# 005_PowerRele_OnOff.net
KiCad netlist of a schematic drawn in Altium Designer
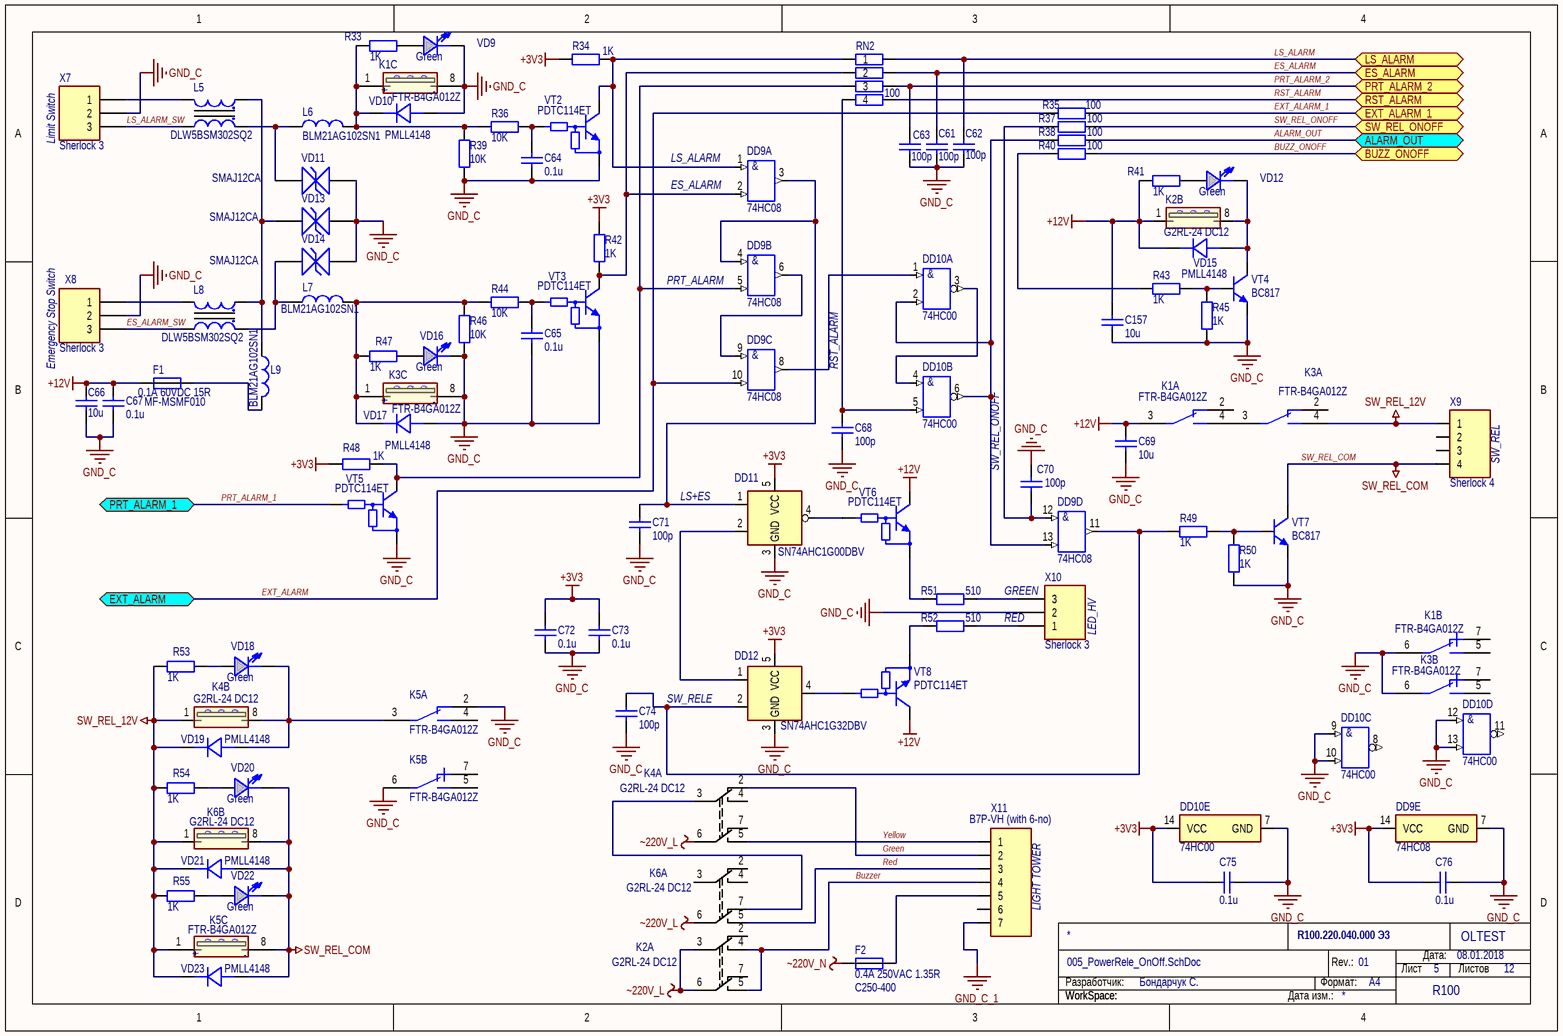
[diagram p0: 005_PowerRele_OnOff.SchDoc]

(export (version "E")
  (design (tool "Eeschema 10.0.6"))
  (components
    (comp (ref "C61")
      (value "100p")
      (footprint "mainLib:SMD_C_0603")
      (description "SMD C 0603 MURATA 100V 5% NP0")
      (fields (field (name "PARTNUMBER") "GRM1885C2A101JA01") (field (name "MANUFACTURER") "MURATA"))
      (libsource (lib "mainRCLib") (part "C0603 100p 100V 5%"))
    )
    (comp (ref "C62")
      (value "100p")
      (footprint "mainLib:SMD_C_0603")
      (description "SMD C 0603 MURATA 100V 5% NP0")
      (fields (field (name "PARTNUMBER") "GRM1885C2A101JA01") (field (name "MANUFACTURER") "MURATA"))
      (libsource (lib "mainRCLib") (part "C0603 100p 100V 5%"))
    )
    (comp (ref "C63")
      (value "100p")
      (footprint "mainLib:SMD_C_0603")
      (description "SMD C 0603 MURATA 100V 5% NP0")
      (fields (field (name "PARTNUMBER") "GRM1885C2A101JA01") (field (name "MANUFACTURER") "MURATA"))
      (libsource (lib "mainRCLib") (part "C0603 100p 100V 5%"))
    )
    (comp (ref "C64")
      (value "0.1u")
      (footprint "mainLib:SMD_C_0603")
      (description "SMD C 0603 MURATA 50V 10% X7R")
      (fields (field (name "PARTNUMBER") "GRM188R71H104K") (field (name "MANUFACTURER") "MURATA"))
      (libsource (lib "mainRCLib") (part "C0603 0.1u 50V 10%"))
    )
    (comp (ref "C65")
      (value "0.1u")
      (footprint "mainLib:SMD_C_0603")
      (description "SMD C 0603 MURATA 50V 10% X7R")
      (fields (field (name "PARTNUMBER") "GRM188R71H104K") (field (name "MANUFACTURER") "MURATA"))
      (libsource (lib "mainRCLib") (part "C0603 0.1u 50V 10%"))
    )
    (comp (ref "C66")
      (value "10u")
      (footprint "mainLib:SMD_C_1206")
      (description "SMD C 1206 MURATA 25V 20% X5R")
      (fields (field (name "PARTNUMBER") "GRM31MR61E106M") (field (name "MANUFACTURER") "MURATA"))
      (libsource (lib "mainRCLib") (part "C1206 10u 25V 20%"))
    )
    (comp (ref "C67")
      (value "0.1u")
      (footprint "mainLib:SMD_C_0603")
      (description "SMD C 0603 MURATA 50V 10% X7R")
      (fields (field (name "PARTNUMBER") "GRM188R71H104K") (field (name "MANUFACTURER") "MURATA"))
      (libsource (lib "mainRCLib") (part "C0603 0.1u 50V 10%"))
    )
    (comp (ref "C68")
      (value "100p")
      (footprint "mainLib:SMD_C_0603")
      (description "SMD C 0603 MURATA 100V 5% NP0")
      (fields (field (name "PARTNUMBER") "GRM1885C2A101JA01") (field (name "MANUFACTURER") "MURATA"))
      (libsource (lib "mainRCLib") (part "C0603 100p 100V 5%"))
    )
    (comp (ref "C69")
      (value "10u")
      (footprint "mainLib:SMD_C_1206")
      (description "SMD C 1206 MURATA 25V 20% X5R")
      (fields (field (name "PARTNUMBER") "GRM31MR61E106M") (field (name "MANUFACTURER") "MURATA"))
      (libsource (lib "mainRCLib") (part "C1206 10u 25V 20%"))
    )
    (comp (ref "C70")
      (value "100p")
      (footprint "mainLib:SMD_C_0603")
      (description "SMD C 0603 MURATA 100V 5% NP0")
      (fields (field (name "PARTNUMBER") "GRM1885C2A101JA01") (field (name "MANUFACTURER") "MURATA"))
      (libsource (lib "mainRCLib") (part "C0603 100p 100V 5%"))
    )
    (comp (ref "C71")
      (value "100p")
      (footprint "mainLib:SMD_C_0603")
      (description "SMD C 0603 MURATA 100V 5% NP0")
      (fields (field (name "PARTNUMBER") "GRM1885C2A101JA01") (field (name "MANUFACTURER") "MURATA"))
      (libsource (lib "mainRCLib") (part "C0603 100p 100V 5%"))
    )
    (comp (ref "C72")
      (value "0.1u")
      (footprint "mainLib:SMD_C_0603")
      (description "SMD C 0603 MURATA 50V 10% X7R")
      (fields (field (name "PARTNUMBER") "GRM188R71H104K") (field (name "MANUFACTURER") "MURATA"))
      (libsource (lib "mainRCLib") (part "C0603 0.1u 50V 10%"))
    )
    (comp (ref "C73")
      (value "0.1u")
      (footprint "mainLib:SMD_C_0603")
      (description "SMD C 0603 MURATA 50V 10% X7R")
      (fields (field (name "PARTNUMBER") "GRM188R71H104K") (field (name "MANUFACTURER") "MURATA"))
      (libsource (lib "mainRCLib") (part "C0603 0.1u 50V 10%"))
    )
    (comp (ref "C74")
      (value "100p")
      (footprint "mainLib:SMD_C_0603")
      (description "SMD C 0603 MURATA 100V 5% NP0")
      (fields (field (name "PARTNUMBER") "GRM1885C2A101JA01") (field (name "MANUFACTURER") "MURATA"))
      (libsource (lib "mainRCLib") (part "C0603 100p 100V 5%"))
    )
    (comp (ref "C75")
      (value "0.1u")
      (footprint "mainLib:SMD_C_0603")
      (description "SMD C 0603 MURATA 50V 10% X7R")
      (fields (field (name "PARTNUMBER") "GRM188R71H104K") (field (name "MANUFACTURER") "MURATA"))
      (libsource (lib "mainRCLib") (part "C0603 0.1u 50V 10%"))
    )
    (comp (ref "C76")
      (value "0.1u")
      (footprint "mainLib:SMD_C_0603")
      (description "SMD C 0603 MURATA 50V 10% X7R")
      (fields (field (name "PARTNUMBER") "GRM188R71H104K") (field (name "MANUFACTURER") "MURATA"))
      (libsource (lib "mainRCLib") (part "C0603 0.1u 50V 10%"))
    )
    (comp (ref "C157")
      (value "10u")
      (footprint "mainLib:SMD_C_1206")
      (description "SMD C 1206 MURATA 25V 20% X5R")
      (fields (field (name "PARTNUMBER") "GRM31MR61E106M") (field (name "MANUFACTURER") "MURATA"))
      (libsource (lib "mainRCLib") (part "C1206 10u 25V 20%"))
    )
    (comp (ref "DD9")
      (value "74HC08")
      (footprint "mainLib:TSSOP14")
      (description "Quad 2-Input Positive-NAND Gates, PW0014A")
      (fields
        (field (name "GENERIC PART NUMBER") "SN74HC00")
        (field (name "MANUFACTURER") "Texas Instruments")
      )
      (libsource (lib "mainLib") (part "74HC08"))
    )
    (comp (ref "DD10")
      (value "74HC00")
      (footprint "mainLib:TSSOP14")
      (description "Quad 2-Input Positive-NAND Gates, PW0014A")
      (fields
        (field (name "GENERIC PART NUMBER") "SN74HC00")
        (field (name "MANUFACTURER") "Texas Instruments")
      )
      (libsource (lib "mainLib") (part "74HC00"))
    )
    (comp (ref "DD11")
      (value "SN74AHC1G00DBV")
      (footprint "mainLib:SOT-23(DBV)")
      (description "2-in NAND")
      (fields (field (name "MANUFACTURER") "Texas Instruments"))
      (libsource (lib "mainLib") (part "SN74AHC1G00DBV"))
    )
    (comp (ref "DD12")
      (value "SN74AHC1G32DBV")
      (footprint "mainLib:SOT-23(DBV)")
      (description "2-in OR")
      (fields (field (name "MANUFACTURER") "Texas Instruments"))
      (libsource (lib "mainLib") (part "SN74AHC1G32DBV"))
    )
    (comp (ref "F1")
      (value "0.1A 60VDC 15R")
      (footprint "mainLib:MF-MSMF010")
      (description "PTC Resettable Fusses 0.1A 60VDC 15R")
      (fields (field (name "MANUFACTURER") "BOURNS") (field (name "PARTNUMBER") "MF-MSMF010"))
      (libsource (lib "mainLib") (part "MF-MSMF010 (0.1A 60VDC 15R)"))
    )
    (comp (ref "F2")
      (value "0.4A 250VAC 1.35R")
      (footprint "mainLib:C250-400")
      (description "PTC Resettable Fusses 0.4A 250VAC 1.35R")
      (fields
        (field (name "MANUFACTURER") "SEA&LAND ELECTRONIC CORP.")
        (field (name "PARTNUMBER") "C250-400")
      )
      (libsource (lib "mainLib") (part "C250-400 (0.4A 250VAC 1.35R)"))
    )
    (comp (ref "K1")
      (value "FTR-B4GA012Z")
      (footprint "mainLib:FTR-B4GA")
      (description "250VAC 1A DPDT 12VDC")
      (fields (field (name "MANUFACTURER") "Fujitsu"))
      (libsource (lib "mainLib") (part "FTR-B4GA012Z"))
    )
    (comp (ref "K2")
      (value "G2RL-24 DC12")
      (footprint "mainLib:G2RL")
      (description "440VAC 8A DPDT 12VDC")
      (fields (field (name "MANUFACTURER") "Omron"))
      (libsource (lib "") (part "G2RL-24 DC12_1"))
    )
    (comp (ref "K3")
      (value "FTR-B4GA012Z")
      (footprint "mainLib:FTR-B4GA")
      (description "250VAC 1A DPDT 12VDC")
      (fields (field (name "MANUFACTURER") "Fujitsu"))
      (libsource (lib "mainLib") (part "FTR-B4GA012Z"))
    )
    (comp (ref "K4")
      (value "G2RL-24 DC12")
      (footprint "mainLib:G2RL")
      (description "440VAC 8A DPDT 12VDC")
      (fields (field (name "MANUFACTURER") "Omron"))
      (libsource (lib "") (part "G2RL-24 DC12_1"))
    )
    (comp (ref "K5")
      (value "FTR-B4GA012Z")
      (footprint "mainLib:FTR-B4GA")
      (description "250VAC 1A DPDT 12VDC")
      (fields (field (name "MANUFACTURER") "Fujitsu"))
      (libsource (lib "mainLib") (part "FTR-B4GA012Z"))
    )
    (comp (ref "K6")
      (value "G2RL-24 DC12")
      (footprint "mainLib:G2RL")
      (description "440VAC 8A DPDT 12VDC")
      (fields (field (name "MANUFACTURER") "Omron"))
      (libsource (lib "mainLib") (part "G2RL-24 DC12"))
    )
    (comp (ref "L5")
      (value "DLW5BSM302SQ2")
      (footprint "mainLib:DLW5BS(AH)")
      (description "SMD Common Mode Choke Coil 0.5A Z = 3000 Ohm / 100 MHz")
      (fields (field (name "MANUFACTURER") "MURATA"))
      (libsource (lib "mainLib") (part "DLW5BSM302SQ2"))
    )
    (comp (ref "L6")
      (value "BLM21AG102SN1")
      (footprint "mainLib:SMD_L_L2_W1.25")
      (description "1000R 0.6A (100MHz)")
      (fields (field (name "MANUFACTURER") "TDK"))
      (libsource (lib "mainLib") (part "BLM21AG102SN1"))
    )
    (comp (ref "L7")
      (value "BLM21AG102SN1")
      (footprint "mainLib:SMD_L_L2_W1.25")
      (description "1000R 0.6A (100MHz)")
      (fields (field (name "MANUFACTURER") "TDK"))
      (libsource (lib "mainLib") (part "BLM21AG102SN1"))
    )
    (comp (ref "L8")
      (value "DLW5BSM302SQ2")
      (footprint "mainLib:DLW5BS(AH)")
      (description "SMD Common Mode Choke Coil 0.5A Z = 3000 Ohm / 100 MHz")
      (fields (field (name "MANUFACTURER") "MURATA"))
      (libsource (lib "mainLib") (part "DLW5BSM302SQ2"))
    )
    (comp (ref "L9")
      (value "BLM21AG102SN1")
      (footprint "mainLib:SMD_L_L2_W1.25")
      (description "1000R 0.6A (100MHz)")
      (fields (field (name "MANUFACTURER") "TDK"))
      (libsource (lib "mainLib") (part "BLM21AG102SN1"))
    )
    (comp (ref "R33")
      (value "1K")
      (footprint "mainLib:SMD_R_1206")
      (description "SMD R 1206 VISHAY 0.25W 200V 1% 100ppm")
      (fields (field (name "PARTNUMBER") "CRCW12061K00FK") (field (name "MANUFACTURER") "VISHAY"))
      (libsource (lib "mainRCLib") (part "R1206 1K 1%"))
    )
    (comp (ref "R34")
      (value "1K")
      (footprint "mainLib:SMD_R_0603")
      (description "SMD R 0603 VISHAY 0.1W 75V 1% 100ppm")
      (fields (field (name "PARTNUMBER") "CRCW06031K00FK") (field (name "MANUFACTURER") "VISHAY"))
      (libsource (lib "mainRCLib") (part "R0603 1K 1%"))
    )
    (comp (ref "R35")
      (value "100")
      (footprint "SMD_R_0603")
      (description "SMD R 0603 VISHAY 0.1W 75V 1% 100ppm")
      (fields (field (name "PARTNUMBER") "CRCW0603100RFK") (field (name "MANUFACTURER") "VISHAY"))
      (libsource (lib "mainRCLib") (part "R0603 100 1%"))
    )
    (comp (ref "R36")
      (value "10K")
      (footprint "SMD_R_0603")
      (description "SMD R 0603 VISHAY 0.1W 75V 1% 100ppm")
      (fields (field (name "PARTNUMBER") "CRCW060310K0FK") (field (name "MANUFACTURER") "VISHAY"))
      (libsource (lib "") (part "R0603 10К 1%_1"))
    )
    (comp (ref "R37")
      (value "100")
      (footprint "SMD_R_0603")
      (description "SMD R 0603 VISHAY 0.1W 75V 1% 100ppm")
      (fields (field (name "PARTNUMBER") "CRCW0603100RFK") (field (name "MANUFACTURER") "VISHAY"))
      (libsource (lib "mainRCLib") (part "R0603 100 1%"))
    )
    (comp (ref "R38")
      (value "100")
      (footprint "SMD_R_0603")
      (description "SMD R 0603 VISHAY 0.1W 75V 1% 100ppm")
      (fields (field (name "PARTNUMBER") "CRCW0603100RFK") (field (name "MANUFACTURER") "VISHAY"))
      (libsource (lib "mainRCLib") (part "R0603 100 1%"))
    )
    (comp (ref "R39")
      (value "10K")
      (footprint "SMD_R_0603")
      (description "SMD R 0603 VISHAY 0.1W 75V 1% 100ppm")
      (fields (field (name "PARTNUMBER") "CRCW060310K0FK") (field (name "MANUFACTURER") "VISHAY"))
      (libsource (lib "mainRCLib") (part "R0603 10К 1%"))
    )
    (comp (ref "R40")
      (value "100")
      (footprint "SMD_R_0603")
      (description "SMD R 0603 VISHAY 0.1W 75V 1% 100ppm")
      (fields (field (name "PARTNUMBER") "CRCW0603100RFK") (field (name "MANUFACTURER") "VISHAY"))
      (libsource (lib "mainRCLib") (part "R0603 100 1%"))
    )
    (comp (ref "R41")
      (value "1K")
      (footprint "mainLib:SMD_R_1206")
      (description "SMD R 1206 VISHAY 0.25W 200V 1% 100ppm")
      (fields (field (name "PARTNUMBER") "CRCW12061K00FK") (field (name "MANUFACTURER") "VISHAY"))
      (libsource (lib "mainRCLib") (part "R1206 1K 1%"))
    )
    (comp (ref "R42")
      (value "1K")
      (footprint "mainLib:SMD_R_0603")
      (description "SMD R 0603 VISHAY 0.1W 75V 1% 100ppm")
      (fields (field (name "PARTNUMBER") "CRCW06031K00FK") (field (name "MANUFACTURER") "VISHAY"))
      (libsource (lib "") (part "R0603 1K 1%_1"))
    )
    (comp (ref "R43")
      (value "1K")
      (footprint "mainLib:SMD_R_0805")
      (description "SMD R 0805 VISHAY 0.125W 150V 1% 100ppm")
      (fields (field (name "PARTNUMBER") "CRCW08051K00FK") (field (name "MANUFACTURER") "VISHAY"))
      (libsource (lib "mainRCLib") (part "R0805 1K 1%"))
    )
    (comp (ref "R44")
      (value "10K")
      (footprint "SMD_R_0603")
      (description "SMD R 0603 VISHAY 0.1W 75V 1% 100ppm")
      (fields (field (name "PARTNUMBER") "CRCW060310K0FK") (field (name "MANUFACTURER") "VISHAY"))
      (libsource (lib "") (part "R0603 10К 1%_1"))
    )
    (comp (ref "R45")
      (value "1K")
      (footprint "mainLib:SMD_R_0805")
      (description "SMD R 0805 VISHAY 0.125W 150V 1% 100ppm")
      (fields (field (name "PARTNUMBER") "CRCW08051K00FK") (field (name "MANUFACTURER") "VISHAY"))
      (libsource (lib "") (part "R0805 1K 1%_1"))
    )
    (comp (ref "R46")
      (value "10K")
      (footprint "SMD_R_0603")
      (description "SMD R 0603 VISHAY 0.1W 75V 1% 100ppm")
      (fields (field (name "PARTNUMBER") "CRCW060310K0FK") (field (name "MANUFACTURER") "VISHAY"))
      (libsource (lib "mainRCLib") (part "R0603 10К 1%"))
    )
    (comp (ref "R47")
      (value "1K")
      (footprint "mainLib:SMD_R_1206")
      (description "SMD R 1206 VISHAY 0.25W 200V 1% 100ppm")
      (fields (field (name "PARTNUMBER") "CRCW12061K00FK") (field (name "MANUFACTURER") "VISHAY"))
      (libsource (lib "mainRCLib") (part "R1206 1K 1%"))
    )
    (comp (ref "R48")
      (value "1K")
      (footprint "mainLib:SMD_R_0603")
      (description "SMD R 0603 VISHAY 0.1W 75V 1% 100ppm")
      (fields (field (name "PARTNUMBER") "CRCW06031K00FK") (field (name "MANUFACTURER") "VISHAY"))
      (libsource (lib "mainRCLib") (part "R0603 1K 1%"))
    )
    (comp (ref "R49")
      (value "1K")
      (footprint "mainLib:SMD_R_0805")
      (description "SMD R 0805 VISHAY 0.125W 150V 1% 100ppm")
      (fields (field (name "PARTNUMBER") "CRCW08051K00FK") (field (name "MANUFACTURER") "VISHAY"))
      (libsource (lib "mainRCLib") (part "R0805 1K 1%"))
    )
    (comp (ref "R50")
      (value "1K")
      (footprint "mainLib:SMD_R_0805")
      (description "SMD R 0805 VISHAY 0.125W 150V 1% 100ppm")
      (fields (field (name "PARTNUMBER") "CRCW08051K00FK") (field (name "MANUFACTURER") "VISHAY"))
      (libsource (lib "") (part "R0805 1K 1%_1"))
    )
    (comp (ref "R51")
      (value "510")
      (footprint "mainLib:SMD_R_1206")
      (description "SMD R 1206 VISHAY 0.25W 200V 1% 100ppm")
      (fields (field (name "PARTNUMBER") "CRCW1206510RFK") (field (name "MANUFACTURER") "VISHAY"))
      (libsource (lib "mainRCLib") (part "R1206 510 1%"))
    )
    (comp (ref "R52")
      (value "510")
      (footprint "mainLib:SMD_R_1206")
      (description "SMD R 1206 VISHAY 0.25W 200V 1% 100ppm")
      (fields (field (name "PARTNUMBER") "CRCW1206510RFK") (field (name "MANUFACTURER") "VISHAY"))
      (libsource (lib "mainRCLib") (part "R1206 510 1%"))
    )
    (comp (ref "R53")
      (value "1K")
      (footprint "mainLib:SMD_R_1206")
      (description "SMD R 1206 VISHAY 0.25W 200V 1% 100ppm")
      (fields (field (name "PARTNUMBER") "CRCW12061K00FK") (field (name "MANUFACTURER") "VISHAY"))
      (libsource (lib "mainRCLib") (part "R1206 1K 1%"))
    )
    (comp (ref "R54")
      (value "1K")
      (footprint "mainLib:SMD_R_1206")
      (description "SMD R 1206 VISHAY 0.25W 200V 1% 100ppm")
      (fields (field (name "PARTNUMBER") "CRCW12061K00FK") (field (name "MANUFACTURER") "VISHAY"))
      (libsource (lib "mainRCLib") (part "R1206 1K 1%"))
    )
    (comp (ref "R55")
      (value "1K")
      (footprint "mainLib:SMD_R_1206")
      (description "SMD R 1206 VISHAY 0.25W 200V 1% 100ppm")
      (fields (field (name "PARTNUMBER") "CRCW12061K00FK") (field (name "MANUFACTURER") "VISHAY"))
      (libsource (lib "mainRCLib") (part "R1206 1K 1%"))
    )
    (comp (ref "RN2")
      (value "100")
      (footprint "mainLib:CRA06S")
      (description "SMD RESISTOR ARRAY VISHAY 0.063W 50V 1% 100ppm")
      (fields (field (name "PARTNUMBER") "CRA06S083100RF") (field (name "MANUFACTURER") "VISHAY"))
      (libsource (lib "mainRCLib") (part "CRA06S 4x100 1%"))
    )
    (comp (ref "VD9")
      (value "Green")
      (footprint "mainLib:SMD_LED_LL_Green")
      (description "LED Green SMD")
      (fields (field (name "PARTNUMBER") "LL-S172GC-2A") (field (name "MANUFACTURER") "Lucky Light"))
      (libsource (lib "mainLib") (part "LL-S172GC-2A"))
    )
    (comp (ref "VD10")
      (value "PMLL4148")
      (footprint "mainLib:SOD80C")
      (description "If=0.2A, Vf=1V Vrrm=100V Diode (SOD80C)")
      (fields (field (name "MANUFACTURER") "NXP Semiconductors"))
      (libsource (lib "mainLib") (part "PMLL4148"))
    )
    (comp (ref "VD11")
      (value "SMAJ12CA")
      (footprint "mainLib:DO-214AC noPolarity")
      (description "400W 12V  Transient Voltage Suppressor, Bidirectional")
      (fields (field (name "MANUFACTURER") "LITTELFUSE"))
      (libsource (lib "mainLib") (part "SMAJ12CA"))
    )
    (comp (ref "VD12")
      (value "Green")
      (footprint "mainLib:SMD_LED_LL_Green")
      (description "LED Green SMD")
      (fields (field (name "PARTNUMBER") "LL-S172GC-2A") (field (name "MANUFACTURER") "Lucky Light"))
      (libsource (lib "mainLib") (part "LL-S172GC-2A"))
    )
    (comp (ref "VD13")
      (value "SMAJ12CA")
      (footprint "mainLib:DO-214AC noPolarity")
      (description "400W 12V  Transient Voltage Suppressor, Bidirectional")
      (fields (field (name "MANUFACTURER") "LITTELFUSE"))
      (libsource (lib "mainLib") (part "SMAJ12CA"))
    )
    (comp (ref "VD14")
      (value "SMAJ12CA")
      (footprint "mainLib:DO-214AC noPolarity")
      (description "400W 12V  Transient Voltage Suppressor, Bidirectional")
      (fields (field (name "MANUFACTURER") "LITTELFUSE"))
      (libsource (lib "mainLib") (part "SMAJ12CA"))
    )
    (comp (ref "VD15")
      (value "PMLL4148")
      (footprint "mainLib:SOD80C")
      (description "If=0.2A, Vf=1V Vrrm=100V Diode (SOD80C)")
      (fields (field (name "MANUFACTURER") "NXP Semiconductors"))
      (libsource (lib "mainLib") (part "PMLL4148"))
    )
    (comp (ref "VD16")
      (value "Green")
      (footprint "mainLib:SMD_LED_LL_Green")
      (description "LED Green SMD")
      (fields (field (name "PARTNUMBER") "LL-S172GC-2A") (field (name "MANUFACTURER") "Lucky Light"))
      (libsource (lib "mainLib") (part "LL-S172GC-2A"))
    )
    (comp (ref "VD17")
      (value "PMLL4148")
      (footprint "mainLib:SOD80C")
      (description "If=0.2A, Vf=1V Vrrm=100V Diode (SOD80C)")
      (fields (field (name "MANUFACTURER") "NXP Semiconductors"))
      (libsource (lib "mainLib") (part "PMLL4148"))
    )
    (comp (ref "VD18")
      (value "Green")
      (footprint "mainLib:SMD_LED_LL_Green")
      (description "LED Green SMD")
      (fields (field (name "PARTNUMBER") "LL-S172GC-2A") (field (name "MANUFACTURER") "Lucky Light"))
      (libsource (lib "mainLib") (part "LL-S172GC-2A"))
    )
    (comp (ref "VD19")
      (value "PMLL4148")
      (footprint "mainLib:SOD80C")
      (description "If=0.2A, Vf=1V Vrrm=100V Diode (SOD80C)")
      (fields (field (name "MANUFACTURER") "NXP Semiconductors"))
      (libsource (lib "mainLib") (part "PMLL4148"))
    )
    (comp (ref "VD20")
      (value "Green")
      (footprint "mainLib:SMD_LED_LL_Green")
      (description "LED Green SMD")
      (fields (field (name "PARTNUMBER") "LL-S172GC-2A") (field (name "MANUFACTURER") "Lucky Light"))
      (libsource (lib "mainLib") (part "LL-S172GC-2A"))
    )
    (comp (ref "VD21")
      (value "PMLL4148")
      (footprint "mainLib:SOD80C")
      (description "If=0.2A, Vf=1V Vrrm=100V Diode (SOD80C)")
      (fields (field (name "MANUFACTURER") "NXP Semiconductors"))
      (libsource (lib "mainLib") (part "PMLL4148"))
    )
    (comp (ref "VD22")
      (value "Green")
      (footprint "mainLib:SMD_LED_LL_Green")
      (description "LED Green SMD")
      (fields (field (name "PARTNUMBER") "LL-S172GC-2A") (field (name "MANUFACTURER") "Lucky Light"))
      (libsource (lib "mainLib") (part "LL-S172GC-2A"))
    )
    (comp (ref "VD23")
      (value "PMLL4148")
      (footprint "mainLib:SOD80C")
      (description "If=0.2A, Vf=1V Vrrm=100V Diode (SOD80C)")
      (fields (field (name "MANUFACTURER") "NXP Semiconductors"))
      (libsource (lib "mainLib") (part "PMLL4148"))
    )
    (comp (ref "VT2")
      (value "PDTC114ET")
      (footprint "mainLib:SOT23-3")
      (description "Digital Transistor (BRT), R1=10 kOhm, R2=10 kOhm, NPN Transistor")
      (fields (field (name "MANUFACTURER") "On Semiconductor"))
      (libsource (lib "mainLib") (part "PDTC114ET"))
    )
    (comp (ref "VT3")
      (value "PDTC114ET")
      (footprint "mainLib:SOT23-3")
      (description "Digital Transistor (BRT), R1=10 kOhm, R2=10 kOhm, NPN Transistor")
      (fields (field (name "MANUFACTURER") "On Semiconductor"))
      (libsource (lib "mainLib") (part "PDTC114ET"))
    )
    (comp (ref "VT4")
      (value "BC817")
      (footprint "mainLib:SOT23-3")
      (description "NPN Silicon, 3-Pin SOT-23")
      (fields (field (name "MANUFACTURER") "NXP"))
      (libsource (lib "mainLib") (part "BC817"))
    )
    (comp (ref "VT5")
      (value "PDTC114ET")
      (footprint "mainLib:SOT23-3")
      (description "Digital Transistor (BRT), R1=10 kOhm, R2=10 kOhm, NPN Transistor")
      (fields (field (name "MANUFACTURER") "On Semiconductor"))
      (libsource (lib "mainLib") (part "PDTC114ET"))
    )
    (comp (ref "VT6")
      (value "PDTC114ET")
      (footprint "mainLib:SOT23-3")
      (description "Digital Transistor (BRT), R1=10 kOhm, R2=10 kOhm, NPN Transistor")
      (fields (field (name "MANUFACTURER") "On Semiconductor"))
      (libsource (lib "mainLib") (part "PDTC114ET"))
    )
    (comp (ref "VT7")
      (value "BC817")
      (footprint "mainLib:SOT23-3")
      (description "NPN Silicon, 3-Pin SOT-23")
      (fields (field (name "MANUFACTURER") "NXP"))
      (libsource (lib "mainLib") (part "BC817"))
    )
    (comp (ref "VT8")
      (value "PDTC114ET")
      (footprint "mainLib:SOT23-3")
      (description "Digital Transistor (BRT), R1=10 kOhm, R2=10 kOhm, NPN Transistor")
      (fields (field (name "MANUFACTURER") "On Semiconductor"))
      (libsource (lib "mainLib") (part "PDTC114ET"))
    )
    (comp (ref "X7")
      (value "Sherlock 3")
      (footprint "mainLib:35362-0350")
      (description "Sherlock 3 Top, 2A 125V 2mm")
      (fields (field (name "PARTNUMBER") "35362-0350") (field (name "MANUFACTURER") "MOLEX"))
      (libsource (lib "") (part "35362-0350_1"))
    )
    (comp (ref "X8")
      (value "Sherlock 3")
      (footprint "mainLib:35362-0350")
      (description "Sherlock 3 Top, 2A 125V 2mm")
      (fields (field (name "PARTNUMBER") "35362-0350") (field (name "MANUFACTURER") "MOLEX"))
      (libsource (lib "") (part "35362-0350_1"))
    )
    (comp (ref "X9")
      (value "Sherlock 4")
      (footprint "35362-0450")
      (description "Sherlock 4 Top, 2A 125V 2mm")
      (fields (field (name "PARTNUMBER") "35362-0450") (field (name "MANUFACTURER") "MOLEX"))
      (libsource (lib "mainLib") (part "35362-0450"))
    )
    (comp (ref "X10")
      (value "Sherlock 3")
      (footprint "mainLib:35362-0350")
      (description "Sherlock 3 Top, 2A 125V 2mm")
      (fields (field (name "PARTNUMBER") "35362-0350") (field (name "MANUFACTURER") "MOLEX"))
      (libsource (lib "mainLib") (part "35362-0350"))
    )
    (comp (ref "X11")
      (value "B7P-VH (with 6-no)")
      (footprint "mainLib:B7P-VH (WITH 6-no)")
      (description "VH 7 конт LS=3.96 10A 250V PCB")
      (fields (field (name "PARTNUMBER") "B7P-VH") (field (name "MANUFACTURER") "JST"))
      (libsource (lib "mainLib") (part "B7P-VH (WITH 6-no)"))
    )
  )
  (nets
    (net (code "1") (name "+3V3") (class "Default")
      (node (ref "C72") (pin "2") (pinfunction "2_2") (pintype "passive"))
      (node (ref "C73") (pin "2") (pinfunction "2_2") (pintype "passive"))
      (node (ref "C75") (pin "1") (pinfunction "1_1") (pintype "passive"))
      (node (ref "C76") (pin "1") (pinfunction "1_1") (pintype "passive"))
      (node (ref "DD10") (pin "14") (pinfunction "VCC_14") (pintype "power_in"))
      (node (ref "DD11") (pin "5") (pinfunction "VCC_5") (pintype "passive"))
      (node (ref "DD12") (pin "5") (pinfunction "VCC_5") (pintype "passive"))
      (node (ref "DD9") (pin "14") (pinfunction "VCC_14") (pintype "power_in"))
      (node (ref "R34") (pin "2") (pinfunction "2_2") (pintype "passive"))
      (node (ref "R42") (pin "2") (pinfunction "2_2") (pintype "passive"))
      (node (ref "R48") (pin "2") (pinfunction "2_2") (pintype "passive"))
    )
    (net (code "2") (name "+12V") (class "Default")
      (node (ref "C157") (pin "2") (pinfunction "2_2") (pintype "passive"))
      (node (ref "C66") (pin "2") (pinfunction "2_2") (pintype "passive"))
      (node (ref "C67") (pin "2") (pinfunction "2_2") (pintype "passive"))
      (node (ref "C69") (pin "2") (pinfunction "2_2") (pintype "passive"))
      (node (ref "F1") (pin "1") (pinfunction "1_1") (pintype "passive"))
      (node (ref "K1") (pin "3") (pinfunction "3_3") (pintype "passive"))
      (node (ref "K2") (pin "1") (pinfunction "1_1") (pintype "passive"))
      (node (ref "R41") (pin "1") (pinfunction "1_1") (pintype "passive"))
      (node (ref "VD15") (pin "2") (pinfunction "CATHODE_2") (pintype "passive"))
      (node (ref "VT6") (pin "3") (pinfunction "C_3") (pintype "passive"))
      (node (ref "VT8") (pin "3") (pinfunction "C_3") (pintype "passive"))
    )
    (net (code "3") (name "/ALARM_OUT") (class "Default")
      (node (ref "R38") (pin "2") (pinfunction "2_2") (pintype "passive"))
    )
    (net (code "4") (name "/BUZZ_ONOFF") (class "Default")
      (node (ref "R40") (pin "2") (pinfunction "2_2") (pintype "passive"))
    )
    (net (code "5") (name "/Buzzer") (class "Default")
      (node (ref "K2") (pin "4") (pinfunction "4_4") (pintype "passive"))
      (node (ref "K2") (pin "5") (pinfunction "5_5") (pintype "passive"))
      (node (ref "X11") (pin "4") (pinfunction "4_4") (pintype "passive"))
    )
    (net (code "6") (name "/ES_ALARM") (class "Default")
      (node (ref "C61") (pin "2") (pinfunction "2_2") (pintype "passive"))
      (node (ref "RN2") (pin "7") (pinfunction "7_7") (pintype "passive"))
    )
    (net (code "7") (name "/ES_ALARM_SW") (class "Default")
      (node (ref "L8") (pin "3") (pinfunction "3_3") (pintype "passive"))
      (node (ref "X8") (pin "3") (pinfunction "3_3") (pintype "passive"))
    )
    (net (code "8") (name "/EXT_ALARM") (class "Default")
      (node (ref "DD9") (pin "10") (pinfunction "3B_10") (pintype "input"))
      (node (ref "R35") (pin "1") (pinfunction "1_1") (pintype "passive"))
    )
    (net (code "9") (name "/EXT_ALARM_1") (class "Default")
      (node (ref "R35") (pin "2") (pinfunction "2_2") (pintype "passive"))
    )
    (net (code "10") (name "/Green") (class "Default")
      (node (ref "K4") (pin "2") (pinfunction "2_2") (pintype "passive"))
      (node (ref "X11") (pin "2") (pinfunction "2_2") (pintype "passive"))
    )
    (net (code "11") (name "/LS_ALARM") (class "Default")
      (node (ref "C62") (pin "2") (pinfunction "2_2") (pintype "passive"))
      (node (ref "RN2") (pin "8") (pinfunction "8_8") (pintype "passive"))
    )
    (net (code "12") (name "/LS_ALARM_SW") (class "Default")
      (node (ref "L5") (pin "3") (pinfunction "3_3") (pintype "passive"))
      (node (ref "X7") (pin "3") (pinfunction "3_3") (pintype "passive"))
    )
    (net (code "13") (name "/PRT_ALARM_1") (class "Default")
      (node (ref "VT5") (pin "1") (pinfunction "B_1") (pintype "passive"))
    )
    (net (code "14") (name "/PRT_ALARM_2") (class "Default")
      (node (ref "C63") (pin "2") (pinfunction "2_2") (pintype "passive"))
      (node (ref "RN2") (pin "6") (pinfunction "6_6") (pintype "passive"))
    )
    (net (code "15") (name "/RST_ALARM") (class "Default")
      (node (ref "RN2") (pin "5") (pinfunction "5_5") (pintype "passive"))
    )
    (net (code "16") (name "/Red") (class "Default")
      (node (ref "K6") (pin "5") (pinfunction "5_5") (pintype "passive"))
      (node (ref "X11") (pin "3") (pinfunction "3_3") (pintype "passive"))
    )
    (net (code "17") (name "/SW_REL_ONOFF") (class "Default")
      (node (ref "R37") (pin "2") (pinfunction "2_2") (pintype "passive"))
    )
    (net (code "18") (name "/Yellow") (class "Default")
      (node (ref "K4") (pin "5") (pinfunction "5_5") (pintype "passive"))
      (node (ref "X11") (pin "1") (pinfunction "1_1") (pintype "passive"))
    )
    (net (code "19") (name "GND_C") (class "Default")
      (node (ref "C157") (pin "1") (pinfunction "1_1") (pintype "passive"))
      (node (ref "C61") (pin "1") (pinfunction "1_1") (pintype "passive"))
      (node (ref "C62") (pin "1") (pinfunction "1_1") (pintype "passive"))
      (node (ref "C63") (pin "1") (pinfunction "1_1") (pintype "passive"))
      (node (ref "C64") (pin "1") (pinfunction "1_1") (pintype "passive"))
      (node (ref "C65") (pin "1") (pinfunction "1_1") (pintype "passive"))
      (node (ref "C66") (pin "1") (pinfunction "1_1") (pintype "passive"))
      (node (ref "C67") (pin "1") (pinfunction "1_1") (pintype "passive"))
      (node (ref "C68") (pin "1") (pinfunction "1_1") (pintype "passive"))
      (node (ref "C69") (pin "1") (pinfunction "1_1") (pintype "passive"))
      (node (ref "C70") (pin "2") (pinfunction "2_2") (pintype "passive"))
      (node (ref "C71") (pin "1") (pinfunction "1_1") (pintype "passive"))
      (node (ref "C72") (pin "1") (pinfunction "1_1") (pintype "passive"))
      (node (ref "C73") (pin "1") (pinfunction "1_1") (pintype "passive"))
      (node (ref "C74") (pin "2") (pinfunction "2_2") (pintype "passive"))
      (node (ref "C75") (pin "2") (pinfunction "2_2") (pintype "passive"))
      (node (ref "C76") (pin "2") (pinfunction "2_2") (pintype "passive"))
      (node (ref "DD10") (pin "10") (pinfunction "3B_10") (pintype "input"))
      (node (ref "DD10") (pin "12") (pinfunction "4A_12") (pintype "input"))
      (node (ref "DD10") (pin "13") (pinfunction "4B_13") (pintype "input"))
      (node (ref "DD10") (pin "7") (pinfunction "GND_7") (pintype "power_in"))
      (node (ref "DD10") (pin "9") (pinfunction "3A_9") (pintype "input"))
      (node (ref "DD11") (pin "3") (pinfunction "GND_3") (pintype "passive"))
      (node (ref "DD12") (pin "3") (pinfunction "GND_3") (pintype "passive"))
      (node (ref "DD9") (pin "7") (pinfunction "GND_7") (pintype "power_in"))
      (node (ref "K1") (pin "6") (pinfunction "6_6") (pintype "passive"))
      (node (ref "K1") (pin "8") (pinfunction "8_8") (pintype "passive"))
      (node (ref "K3") (pin "6") (pinfunction "6_6") (pintype "passive"))
      (node (ref "K3") (pin "8") (pinfunction "8_8") (pintype "passive"))
      (node (ref "K5") (pin "2") (pinfunction "2_2") (pintype "passive"))
      (node (ref "K5") (pin "6") (pinfunction "6_6") (pintype "passive"))
      (node (ref "R39") (pin "1") (pinfunction "1_1") (pintype "passive"))
      (node (ref "R45") (pin "1") (pinfunction "1_1") (pintype "passive"))
      (node (ref "R46") (pin "1") (pinfunction "1_1") (pintype "passive"))
      (node (ref "R50") (pin "1") (pinfunction "1_1") (pintype "passive"))
      (node (ref "VD10") (pin "1") (pinfunction "ANODE_1") (pintype "passive"))
      (node (ref "VD11") (pin "2") (pinfunction "2_2") (pintype "passive"))
      (node (ref "VD13") (pin "2") (pinfunction "2_2") (pintype "passive"))
      (node (ref "VD14") (pin "2") (pinfunction "2_2") (pintype "passive"))
      (node (ref "VD16") (pin "2") (pinfunction "CATHODE_2") (pintype "passive"))
      (node (ref "VD17") (pin "1") (pinfunction "ANODE_1") (pintype "passive"))
      (node (ref "VD9") (pin "2") (pinfunction "CATHODE_2") (pintype "passive"))
      (node (ref "VT2") (pin "2") (pinfunction "E_2") (pintype "passive"))
      (node (ref "VT3") (pin "2") (pinfunction "E_2") (pintype "passive"))
      (node (ref "VT4") (pin "2") (pinfunction "E_2") (pintype "passive"))
      (node (ref "VT5") (pin "2") (pinfunction "E_2") (pintype "passive"))
      (node (ref "VT7") (pin "2") (pinfunction "E_2") (pintype "passive"))
      (node (ref "X10") (pin "2") (pinfunction "2_2") (pintype "passive"))
      (node (ref "X7") (pin "2") (pinfunction "2_2") (pintype "passive"))
      (node (ref "X8") (pin "2") (pinfunction "2_2") (pintype "passive"))
    )
    (net (code "20") (name "GND_C_1") (class "Default")
      (node (ref "X11") (pin "7") (pinfunction "7_7") (pintype "passive"))
    )
    (net (code "21") (name "Net-(DD9A-1A)") (class "Default")
      (node (ref "DD9") (pin "1") (pinfunction "1A_1") (pintype "input"))
      (node (ref "R34") (pin "1") (pinfunction "1_1") (pintype "passive"))
      (node (ref "RN2") (pin "1") (pinfunction "1_1") (pintype "passive"))
      (node (ref "VT2") (pin "3") (pinfunction "C_3") (pintype "passive"))
    )
    (net (code "22") (name "Net-(DD9A-1B)") (class "Default")
      (node (ref "DD9") (pin "2") (pinfunction "1B_2") (pintype "input"))
      (node (ref "R42") (pin "1") (pinfunction "1_1") (pintype "passive"))
      (node (ref "RN2") (pin "2") (pinfunction "2_2") (pintype "passive"))
      (node (ref "VT3") (pin "3") (pinfunction "C_3") (pintype "passive"))
    )
    (net (code "23") (name "Net-(DD9A-1Y)") (class "Default")
      (node (ref "C71") (pin "2") (pinfunction "2_2") (pintype "passive"))
      (node (ref "DD11") (pin "1") (pintype "passive"))
      (node (ref "DD9") (pin "3") (pinfunction "1Y_3") (pintype "output"))
      (node (ref "DD9") (pin "4") (pinfunction "2A_4") (pintype "input"))
    )
    (net (code "24") (name "Net-(DD9B-2B)") (class "Default")
      (node (ref "DD9") (pin "5") (pinfunction "2B_5") (pintype "input"))
      (node (ref "R48") (pin "1") (pinfunction "1_1") (pintype "passive"))
      (node (ref "RN2") (pin "3") (pinfunction "3_3") (pintype "passive"))
      (node (ref "VT5") (pin "3") (pinfunction "C_3") (pintype "passive"))
    )
    (net (code "25") (name "Net-(DD9B-2Y)") (class "Default")
      (node (ref "DD9") (pin "6") (pinfunction "2Y_6") (pintype "output"))
      (node (ref "DD9") (pin "9") (pinfunction "3A_9") (pintype "input"))
    )
    (net (code "26") (name "Net-(DD9D-4A)") (class "Default")
      (node (ref "C70") (pin "1") (pinfunction "1_1") (pintype "passive"))
      (node (ref "DD9") (pin "12") (pinfunction "4A_12") (pintype "input"))
      (node (ref "R37") (pin "1") (pinfunction "1_1") (pintype "passive"))
    )
    (net (code "27") (name "Net-(DD9D-4Y)") (class "Default")
      (node (ref "C74") (pin "1") (pinfunction "1_1") (pintype "passive"))
      (node (ref "DD12") (pin "2") (pintype "passive"))
      (node (ref "DD9") (pin "11") (pinfunction "4Y_11") (pintype "output"))
      (node (ref "R49") (pin "1") (pinfunction "1_1") (pintype "passive"))
    )
    (net (code "28") (name "Net-(DD10A-1A)") (class "Default")
      (node (ref "DD10") (pin "1") (pinfunction "1A_1") (pintype "input"))
      (node (ref "DD9") (pin "8") (pinfunction "3Y_8") (pintype "output"))
    )
    (net (code "29") (name "Net-(DD10A-1B)") (class "Default")
      (node (ref "DD10") (pin "2") (pinfunction "1B_2") (pintype "input"))
      (node (ref "DD10") (pin "6") (pinfunction "2Y_6") (pintype "output"))
      (node (ref "DD9") (pin "13") (pinfunction "4B_13") (pintype "input"))
      (node (ref "R38") (pin "1") (pinfunction "1_1") (pintype "passive"))
    )
    (net (code "30") (name "Net-(DD10A-1Y)") (class "Default")
      (node (ref "DD10") (pin "3") (pinfunction "1Y_3") (pintype "output"))
      (node (ref "DD10") (pin "4") (pinfunction "2A_4") (pintype "input"))
    )
    (net (code "31") (name "Net-(DD10B-2B)") (class "Default")
      (node (ref "C68") (pin "2") (pinfunction "2_2") (pintype "passive"))
      (node (ref "DD10") (pin "5") (pinfunction "2B_5") (pintype "input"))
      (node (ref "RN2") (pin "4") (pinfunction "4_4") (pintype "passive"))
    )
    (net (code "32") (name "Net-(DD11-Pad2)") (class "Default")
      (node (ref "DD11") (pin "2") (pintype "passive"))
      (node (ref "DD12") (pin "1") (pintype "passive"))
    )
    (net (code "33") (name "Net-(F1-Pad2)") (class "Default")
      (node (ref "F1") (pin "2") (pinfunction "2_2") (pintype "passive"))
      (node (ref "L9") (pin "2") (pinfunction "2_2") (pintype "passive"))
    )
    (net (code "34") (name "Net-(F2-Pad2)") (class "Default")
      (node (ref "F2") (pin "2") (pinfunction "2_2") (pintype "passive"))
      (node (ref "X11") (pin "5") (pinfunction "5_5") (pintype "passive"))
    )
    (net (code "35") (name "Net-(K1-Pad4)") (class "Default")
      (node (ref "K1") (pin "4") (pinfunction "4_4") (pintype "passive"))
      (node (ref "K3") (pin "3") (pinfunction "3_3") (pintype "passive"))
    )
    (net (code "36") (name "Net-(K4-Pad3)") (class "Default")
      (node (ref "K4") (pin "3") (pinfunction "3_3") (pintype "passive"))
      (node (ref "K6") (pin "7") (pinfunction "7_7") (pintype "passive"))
    )
    (net (code "37") (name "Net-(L5-Pad1)") (class "Default")
      (node (ref "L5") (pin "1") (pinfunction "1_1") (pintype "passive"))
      (node (ref "L8") (pin "1") (pinfunction "1_1") (pintype "passive"))
      (node (ref "L9") (pin "1") (pinfunction "1_1") (pintype "passive"))
      (node (ref "VD13") (pin "1") (pinfunction "1_1") (pintype "passive"))
    )
    (net (code "38") (name "Net-(L5-Pad2)") (class "Default")
      (node (ref "L5") (pin "2") (pinfunction "2_2") (pintype "passive"))
      (node (ref "X7") (pin "1") (pinfunction "1_1") (pintype "passive"))
    )
    (net (code "39") (name "Net-(L5-Pad4)") (class "Default")
      (node (ref "L5") (pin "4") (pinfunction "4_4") (pintype "passive"))
      (node (ref "L6") (pin "1") (pinfunction "1_1") (pintype "passive"))
      (node (ref "VD11") (pin "1") (pinfunction "1_1") (pintype "passive"))
    )
    (net (code "40") (name "Net-(L7-Pad1)") (class "Default")
      (node (ref "L7") (pin "1") (pinfunction "1_1") (pintype "passive"))
      (node (ref "L8") (pin "4") (pinfunction "4_4") (pintype "passive"))
      (node (ref "VD14") (pin "1") (pinfunction "1_1") (pintype "passive"))
    )
    (net (code "41") (name "Net-(L8-Pad2)") (class "Default")
      (node (ref "L8") (pin "2") (pinfunction "2_2") (pintype "passive"))
      (node (ref "X8") (pin "1") (pinfunction "1_1") (pintype "passive"))
    )
    (net (code "42") (name "Net-(R40-Pad1)") (class "Default")
      (node (ref "R40") (pin "1") (pinfunction "1_1") (pintype "passive"))
      (node (ref "R43") (pin "1") (pinfunction "1_1") (pintype "passive"))
    )
    (net (code "43") (name "Net-(R51-Pad2)") (class "Default")
      (node (ref "R51") (pin "2") (pinfunction "2_2") (pintype "passive"))
      (node (ref "X10") (pin "3") (pinfunction "3_3") (pintype "passive"))
    )
    (net (code "44") (name "Net-(R52-Pad2)") (class "Default")
      (node (ref "R52") (pin "2") (pinfunction "2_2") (pintype "passive"))
      (node (ref "X10") (pin "1") (pinfunction "1_1") (pintype "passive"))
    )
    (net (code "45") (name "Net-(VD9-ANODE)") (class "Default")
      (node (ref "R33") (pin "2") (pinfunction "2_2") (pintype "passive"))
      (node (ref "VD9") (pin "1") (pinfunction "ANODE_1") (pintype "passive"))
    )
    (net (code "46") (name "Net-(VD10-CATHODE)") (class "Default")
      (node (ref "K1") (pin "1") (pinfunction "1_1") (pintype "passive"))
      (node (ref "L6") (pin "2") (pinfunction "2_2") (pintype "passive"))
      (node (ref "R33") (pin "1") (pinfunction "1_1") (pintype "passive"))
      (node (ref "R36") (pin "1") (pinfunction "1_1") (pintype "passive"))
      (node (ref "R39") (pin "2") (pinfunction "2_2") (pintype "passive"))
      (node (ref "VD10") (pin "2") (pinfunction "CATHODE_2") (pintype "passive"))
    )
    (net (code "47") (name "Net-(VD12-ANODE)") (class "Default")
      (node (ref "R41") (pin "2") (pinfunction "2_2") (pintype "passive"))
      (node (ref "VD12") (pin "1") (pinfunction "ANODE_1") (pintype "passive"))
    )
    (net (code "48") (name "Net-(VD12-CATHODE)") (class "Default")
      (node (ref "K2") (pin "8") (pinfunction "8_8") (pintype "passive"))
      (node (ref "VD12") (pin "2") (pinfunction "CATHODE_2") (pintype "passive"))
      (node (ref "VD15") (pin "1") (pinfunction "ANODE_1") (pintype "passive"))
      (node (ref "VT4") (pin "3") (pinfunction "C_3") (pintype "passive"))
    )
    (net (code "49") (name "Net-(VD16-ANODE)") (class "Default")
      (node (ref "R47") (pin "2") (pinfunction "2_2") (pintype "passive"))
      (node (ref "VD16") (pin "1") (pinfunction "ANODE_1") (pintype "passive"))
    )
    (net (code "50") (name "Net-(VD17-CATHODE)") (class "Default")
      (node (ref "K3") (pin "1") (pinfunction "1_1") (pintype "passive"))
      (node (ref "L7") (pin "2") (pinfunction "2_2") (pintype "passive"))
      (node (ref "R44") (pin "1") (pinfunction "1_1") (pintype "passive"))
      (node (ref "R46") (pin "2") (pinfunction "2_2") (pintype "passive"))
      (node (ref "R47") (pin "1") (pinfunction "1_1") (pintype "passive"))
      (node (ref "VD17") (pin "2") (pinfunction "CATHODE_2") (pintype "passive"))
    )
    (net (code "51") (name "Net-(VD18-ANODE)") (class "Default")
      (node (ref "R53") (pin "2") (pinfunction "2_2") (pintype "passive"))
      (node (ref "VD18") (pin "1") (pinfunction "ANODE_1") (pintype "passive"))
    )
    (net (code "52") (name "Net-(VD18-CATHODE)") (class "Default")
      (node (ref "K4") (pin "8") (pinfunction "8_8") (pintype "passive"))
      (node (ref "K5") (pin "3") (pinfunction "3_3") (pintype "passive"))
      (node (ref "VD18") (pin "2") (pinfunction "CATHODE_2") (pintype "passive"))
      (node (ref "VD19") (pin "1") (pinfunction "ANODE_1") (pintype "passive"))
    )
    (net (code "53") (name "Net-(VD20-ANODE)") (class "Default")
      (node (ref "R54") (pin "2") (pinfunction "2_2") (pintype "passive"))
      (node (ref "VD20") (pin "1") (pinfunction "ANODE_1") (pintype "passive"))
    )
    (net (code "54") (name "Net-(VD22-ANODE)") (class "Default")
      (node (ref "R55") (pin "2") (pinfunction "2_2") (pintype "passive"))
      (node (ref "VD22") (pin "1") (pinfunction "ANODE_1") (pintype "passive"))
    )
    (net (code "55") (name "Net-(VT2-B)") (class "Default")
      (node (ref "C64") (pin "2") (pinfunction "2_2") (pintype "passive"))
      (node (ref "R36") (pin "2") (pinfunction "2_2") (pintype "passive"))
      (node (ref "VT2") (pin "1") (pinfunction "B_1") (pintype "passive"))
    )
    (net (code "56") (name "Net-(VT3-B)") (class "Default")
      (node (ref "C65") (pin "2") (pinfunction "2_2") (pintype "passive"))
      (node (ref "R44") (pin "2") (pinfunction "2_2") (pintype "passive"))
      (node (ref "VT3") (pin "1") (pinfunction "B_1") (pintype "passive"))
    )
    (net (code "57") (name "Net-(VT4-B)") (class "Default")
      (node (ref "R43") (pin "2") (pinfunction "2_2") (pintype "passive"))
      (node (ref "R45") (pin "2") (pinfunction "2_2") (pintype "passive"))
      (node (ref "VT4") (pin "1") (pinfunction "B_1") (pintype "passive"))
    )
    (net (code "58") (name "Net-(VT6-B)") (class "Default")
      (node (ref "DD11") (pin "4") (pintype "passive"))
      (node (ref "VT6") (pin "1") (pinfunction "B_1") (pintype "passive"))
    )
    (net (code "59") (name "Net-(VT6-E)") (class "Default")
      (node (ref "R51") (pin "1") (pinfunction "1_1") (pintype "passive"))
      (node (ref "VT6") (pin "2") (pinfunction "E_2") (pintype "passive"))
    )
    (net (code "60") (name "Net-(VT7-B)") (class "Default")
      (node (ref "R49") (pin "2") (pinfunction "2_2") (pintype "passive"))
      (node (ref "R50") (pin "2") (pinfunction "2_2") (pintype "passive"))
      (node (ref "VT7") (pin "1") (pinfunction "B_1") (pintype "passive"))
    )
    (net (code "61") (name "Net-(VT8-B)") (class "Default")
      (node (ref "DD12") (pin "4") (pintype "passive"))
      (node (ref "VT8") (pin "1") (pinfunction "B_1") (pintype "passive"))
    )
    (net (code "62") (name "Net-(VT8-E)") (class "Default")
      (node (ref "R52") (pin "1") (pinfunction "1_1") (pintype "passive"))
      (node (ref "VT8") (pin "2") (pinfunction "E_2") (pintype "passive"))
    )
    (net (code "63") (name "SW_REL_12V") (class "Default")
      (node (ref "K3") (pin "4") (pinfunction "4_4") (pintype "passive"))
      (node (ref "K4") (pin "1") (pinfunction "1_1") (pintype "passive"))
      (node (ref "K5") (pin "1") (pinfunction "1_1") (pintype "passive"))
      (node (ref "K6") (pin "1") (pinfunction "1_1") (pintype "passive"))
      (node (ref "R53") (pin "1") (pinfunction "1_1") (pintype "passive"))
      (node (ref "R54") (pin "1") (pinfunction "1_1") (pintype "passive"))
      (node (ref "R55") (pin "1") (pinfunction "1_1") (pintype "passive"))
      (node (ref "VD19") (pin "2") (pinfunction "CATHODE_2") (pintype "passive"))
      (node (ref "VD21") (pin "2") (pinfunction "CATHODE_2") (pintype "passive"))
      (node (ref "VD23") (pin "2") (pinfunction "CATHODE_2") (pintype "passive"))
      (node (ref "X9") (pin "1") (pinfunction "1_1") (pintype "passive"))
    )
    (net (code "64") (name "SW_REL_COM") (class "Default")
      (node (ref "K5") (pin "8") (pinfunction "8_8") (pintype "passive"))
      (node (ref "K6") (pin "8") (pinfunction "8_8") (pintype "passive"))
      (node (ref "VD20") (pin "2") (pinfunction "CATHODE_2") (pintype "passive"))
      (node (ref "VD21") (pin "1") (pinfunction "ANODE_1") (pintype "passive"))
      (node (ref "VD22") (pin "2") (pinfunction "CATHODE_2") (pintype "passive"))
      (node (ref "VD23") (pin "1") (pinfunction "ANODE_1") (pintype "passive"))
      (node (ref "VT7") (pin "3") (pinfunction "C_3") (pintype "passive"))
      (node (ref "X9") (pin "4") (pinfunction "4_4") (pintype "passive"))
    )
    (net (code "65") (name "unconnected-(DD10C-3Y-Pad8)") (class "Default")
      (node (ref "DD10") (pin "8") (pinfunction "3Y_8") (pintype "output"))
    )
    (net (code "66") (name "unconnected-(DD10D-4Y-Pad11)") (class "Default")
      (node (ref "DD10") (pin "11") (pinfunction "4Y_11") (pintype "output"))
    )
    (net (code "67") (name "unconnected-(K1-Pad2)") (class "Default")
      (node (ref "K1") (pin "2") (pinfunction "2_2") (pintype "passive"))
    )
    (net (code "68") (name "unconnected-(K1-Pad5)") (class "Default")
      (node (ref "K1") (pin "5") (pinfunction "5_5") (pintype "passive"))
    )
    (net (code "69") (name "unconnected-(K1-Pad7)") (class "Default")
      (node (ref "K1") (pin "7") (pinfunction "7_7") (pintype "passive"))
    )
    (net (code "70") (name "unconnected-(K2-Pad2)") (class "Default")
      (node (ref "K2") (pin "2") (pinfunction "2_2") (pintype "passive"))
    )
    (net (code "71") (name "unconnected-(K2-Pad7)") (class "Default")
      (node (ref "K2") (pin "7") (pinfunction "7_7") (pintype "passive"))
    )
    (net (code "72") (name "unconnected-(K3-Pad2)") (class "Default")
      (node (ref "K3") (pin "2") (pinfunction "2_2") (pintype "passive"))
    )
    (net (code "73") (name "unconnected-(K3-Pad5)") (class "Default")
      (node (ref "K3") (pin "5") (pinfunction "5_5") (pintype "passive"))
    )
    (net (code "74") (name "unconnected-(K3-Pad7)") (class "Default")
      (node (ref "K3") (pin "7") (pinfunction "7_7") (pintype "passive"))
    )
    (net (code "75") (name "unconnected-(K4-Pad4)") (class "Default")
      (node (ref "K4") (pin "4") (pinfunction "4_4") (pintype "passive"))
    )
    (net (code "76") (name "unconnected-(K4-Pad7)") (class "Default")
      (node (ref "K4") (pin "7") (pinfunction "7_7") (pintype "passive"))
    )
    (net (code "77") (name "unconnected-(K5-Pad4)") (class "Default")
      (node (ref "K5") (pin "4") (pinfunction "4_4") (pintype "passive"))
    )
    (net (code "78") (name "unconnected-(K5-Pad5)") (class "Default")
      (node (ref "K5") (pin "5") (pinfunction "5_5") (pintype "passive"))
    )
    (net (code "79") (name "unconnected-(K5-Pad7)") (class "Default")
      (node (ref "K5") (pin "7") (pinfunction "7_7") (pintype "passive"))
    )
    (net (code "80") (name "unconnected-(K6-Pad2)") (class "Default")
      (node (ref "K6") (pin "2") (pinfunction "2_2") (pintype "passive"))
    )
    (net (code "81") (name "unconnected-(K6-Pad3)") (class "Default")
      (node (ref "K6") (pin "3") (pinfunction "3_3") (pintype "passive"))
    )
    (net (code "82") (name "unconnected-(K6-Pad4)") (class "Default")
      (node (ref "K6") (pin "4") (pinfunction "4_4") (pintype "passive"))
    )
    (net (code "83") (name "unconnected-(X9-Pad2)") (class "Default")
      (node (ref "X9") (pin "2") (pinfunction "2_2") (pintype "passive"))
    )
    (net (code "84") (name "unconnected-(X9-Pad3)") (class "Default")
      (node (ref "X9") (pin "3") (pinfunction "3_3") (pintype "passive"))
    )
    (net (code "85") (name "unconnected-(X11-Pad6)") (class "Default")
      (node (ref "X11") (pin "6") (pinfunction "6_6") (pintype "passive"))
    )
    (net (code "86") (name "~220V_L") (class "Default")
      (node (ref "K2") (pin "3") (pinfunction "3_3") (pintype "passive"))
      (node (ref "K2") (pin "6") (pinfunction "6_6") (pintype "passive"))
      (node (ref "K4") (pin "6") (pinfunction "6_6") (pintype "passive"))
      (node (ref "K6") (pin "6") (pinfunction "6_6") (pintype "passive"))
    )
    (net (code "87") (name "~220V_N") (class "Default")
      (node (ref "F2") (pin "1") (pinfunction "1_1") (pintype "passive"))
    )
  )
)
